# balloon-v01.net
KiCad netlist of a schematic drawn in EAGLE
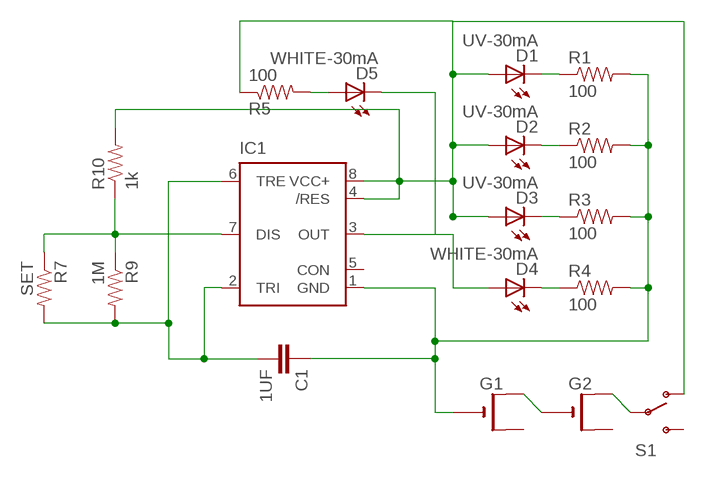
[diagram p0: schematic, sheet 1]

(export (version "E")
  (design (tool "Eeschema 10.0.6"))
  (components
    (comp (ref "C1")
      (value "1UF")
      (footprint "eagle-import:0603-CAP")
      (libsource (lib "eagle-import") (part "CAP0603-CAP"))
    )
    (comp (ref "D1")
      (value "UV-30mA")
      (footprint "eagle-import:CHIPLED_0603")
      (libsource (lib "eagle-import") (part "LEDCHIPLED_0603"))
    )
    (comp (ref "D2")
      (value "UV-30mA")
      (footprint "eagle-import:CHIPLED_0603")
      (libsource (lib "eagle-import") (part "LEDCHIPLED_0603"))
    )
    (comp (ref "D3")
      (value "UV-30mA")
      (footprint "eagle-import:LED5MM")
      (libsource (lib "eagle-import") (part "LED5MM"))
    )
    (comp (ref "D4")
      (value "WHITE-30mA")
      (footprint "eagle-import:LED5MM")
      (libsource (lib "eagle-import") (part "LED5MM"))
    )
    (comp (ref "D5")
      (value "WHITE-30mA")
      (footprint "eagle-import:LED5MM")
      (libsource (lib "eagle-import") (part "LED5MM"))
    )
    (comp (ref "G1")
      (value "CR2032SMT")
      (footprint "eagle-import:CR2032-SMD")
      (libsource (lib "eagle-import") (part "CR2032SMT"))
    )
    (comp (ref "G2")
      (value "CR2032SMT")
      (footprint "eagle-import:CR2032-SMD")
      (libsource (lib "eagle-import") (part "CR2032SMT"))
    )
    (comp (ref "IC1")
      (value "NE555D")
      (footprint "eagle-import:SO08")
      (libsource (lib "eagle-import") (part "NE555D"))
    )
    (comp (ref "R1")
      (value "100")
      (footprint "eagle-import:0603-RES")
      (libsource (lib "eagle-import") (part "RESISTOR0603-RES"))
    )
    (comp (ref "R2")
      (value "100")
      (footprint "eagle-import:0603-RES")
      (libsource (lib "eagle-import") (part "RESISTOR0603-RES"))
    )
    (comp (ref "R3")
      (value "100")
      (footprint "eagle-import:0603-RES")
      (libsource (lib "eagle-import") (part "RESISTOR0603-RES"))
    )
    (comp (ref "R4")
      (value "100")
      (footprint "eagle-import:0603-RES")
      (libsource (lib "eagle-import") (part "RESISTOR0603-RES"))
    )
    (comp (ref "R5")
      (value "100")
      (footprint "eagle-import:0603-RES")
      (libsource (lib "eagle-import") (part "RESISTOR0603-RES"))
    )
    (comp (ref "R7")
      (value "SET")
      (footprint "eagle-import:AXIAL-0.3-KIT")
      (libsource (lib "eagle-import") (part "RESISTORKIT"))
    )
    (comp (ref "R9")
      (value "1M")
      (footprint "eagle-import:0603-RES")
      (libsource (lib "eagle-import") (part "RESISTOR0603-RES"))
    )
    (comp (ref "R10")
      (value "1k")
      (footprint "eagle-import:0603-RES")
      (libsource (lib "eagle-import") (part "RESISTOR0603-RES"))
    )
    (comp (ref "S1")
      (value "SWITCH-SPDT-SMD-A")
      (footprint "eagle-import:SWITCH-SPST-SMD-A")
      (libsource (lib "eagle-import") (part "SWITCH-SPDT-SMD-A"))
    )
  )
  (nets
    (net (code "1") (name "Net-(D1-PadC)") (class "Default")
      (node (ref "D1") (pin "C") (pinfunction "C_C") (pintype "passive"))
      (node (ref "R1") (pin "1") (pinfunction "1_1") (pintype "passive"))
    )
    (net (code "2") (name "Net-(D2-PadC)") (class "Default")
      (node (ref "D2") (pin "C") (pinfunction "C_C") (pintype "passive"))
      (node (ref "R2") (pin "1") (pinfunction "1_1") (pintype "passive"))
    )
    (net (code "3") (name "Net-(D3-C)") (class "Default")
      (node (ref "D3") (pin "K") (pinfunction "C_K") (pintype "passive"))
      (node (ref "R3") (pin "1") (pinfunction "1_1") (pintype "passive"))
    )
    (net (code "4") (name "Net-(D4-C)") (class "Default")
      (node (ref "D4") (pin "K") (pinfunction "C_K") (pintype "passive"))
      (node (ref "R4") (pin "1") (pinfunction "1_1") (pintype "passive"))
    )
    (net (code "5") (name "Net-(D5-C)") (class "Default")
      (node (ref "D4") (pin "A") (pinfunction "A_A") (pintype "passive"))
      (node (ref "D5") (pin "K") (pinfunction "C_K") (pintype "passive"))
      (node (ref "IC1") (pin "3") (pinfunction "OUT_3") (pintype "output"))
    )
    (net (code "6") (name "Net-(D5-PadA)") (class "Default")
      (node (ref "D5") (pin "A") (pinfunction "A_A") (pintype "passive"))
      (node (ref "R5") (pin "2") (pinfunction "2_2") (pintype "passive"))
    )
    (net (code "7") (name "Net-(G1-+)") (class "Default")
      (node (ref "G1") (pin "+$1") (pinfunction "+_+$1") (pintype "passive"))
      (node (ref "G2") (pin "-") (pinfunction "-_-") (pintype "passive"))
    )
    (net (code "8") (name "Net-(G2-+)") (class "Default")
      (node (ref "G2") (pin "+$1") (pinfunction "+_+$1") (pintype "passive"))
      (node (ref "S1") (pin "2") (pinfunction "P_2") (pintype "passive"))
    )
    (net (code "9") (name "Net-(IC1-DIS)") (class "Default")
      (node (ref "IC1") (pin "7") (pinfunction "DIS_7") (pintype "input"))
      (node (ref "R10") (pin "1") (pinfunction "1_1") (pintype "passive"))
      (node (ref "R7") (pin "P$1") (pinfunction "1_P$1") (pintype "passive"))
      (node (ref "R9") (pin "1") (pinfunction "1_1") (pintype "passive"))
    )
    (net (code "10") (name "Net-(IC1-GND)") (class "Default")
      (node (ref "C1") (pin "1") (pinfunction "1_1") (pintype "passive"))
      (node (ref "G1") (pin "-") (pinfunction "-_-") (pintype "passive"))
      (node (ref "IC1") (pin "1") (pinfunction "GND_1") (pintype "power_in"))
      (node (ref "R1") (pin "2") (pinfunction "2_2") (pintype "passive"))
      (node (ref "R2") (pin "2") (pinfunction "2_2") (pintype "passive"))
      (node (ref "R3") (pin "2") (pinfunction "2_2") (pintype "passive"))
      (node (ref "R4") (pin "2") (pinfunction "2_2") (pintype "passive"))
    )
    (net (code "11") (name "Net-(IC1-TRE)") (class "Default")
      (node (ref "C1") (pin "2") (pinfunction "2_2") (pintype "passive"))
      (node (ref "IC1") (pin "2") (pinfunction "TRI_2") (pintype "input"))
      (node (ref "IC1") (pin "6") (pinfunction "TRE_6") (pintype "input"))
      (node (ref "R7") (pin "P$2") (pinfunction "2_P$2") (pintype "passive"))
      (node (ref "R9") (pin "2") (pinfunction "2_2") (pintype "passive"))
    )
    (net (code "12") (name "Net-(IC1-VCC+)") (class "Default")
      (node (ref "D1") (pin "A") (pinfunction "A_A") (pintype "passive"))
      (node (ref "D2") (pin "A") (pinfunction "A_A") (pintype "passive"))
      (node (ref "D3") (pin "A") (pinfunction "A_A") (pintype "passive"))
      (node (ref "IC1") (pin "4") (pinfunction "/RES_4") (pintype "input"))
      (node (ref "IC1") (pin "8") (pinfunction "VCC+_8") (pintype "power_in"))
      (node (ref "R10") (pin "2") (pinfunction "2_2") (pintype "passive"))
      (node (ref "R5") (pin "1") (pinfunction "1_1") (pintype "passive"))
      (node (ref "S1") (pin "1") (pinfunction "O_1") (pintype "passive"))
    )
    (net (code "13") (name "unconnected-(G1-+1-Pad+$2)") (class "Default")
      (node (ref "G1") (pin "+$2") (pinfunction "+1_+$2") (pintype "passive"))
    )
    (net (code "14") (name "unconnected-(G2-+1-Pad+$2)") (class "Default")
      (node (ref "G2") (pin "+$2") (pinfunction "+1_+$2") (pintype "passive"))
    )
    (net (code "15") (name "unconnected-(IC1-CON-Pad5)") (class "Default")
      (node (ref "IC1") (pin "5") (pinfunction "CON_5") (pintype "input"))
    )
    (net (code "16") (name "unconnected-(S1-S-Pad3)") (class "Default")
      (node (ref "S1") (pin "3") (pinfunction "S_3") (pintype "passive"))
    )
  )
)
